# ISO_12V_to_20V.net
KiCad netlist of a schematic drawn in Altium Designer
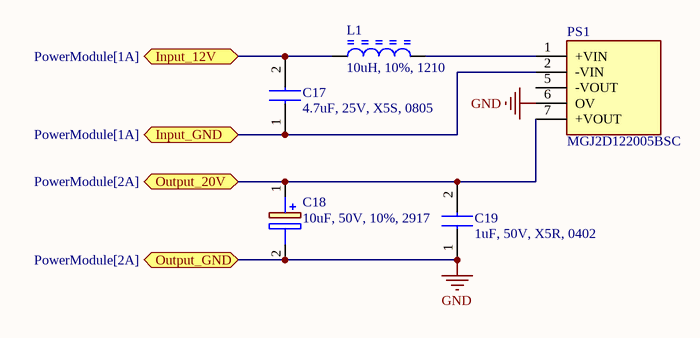
[diagram p0: ISO_12V_to_20V.SchDoc]

(export (version "E")
  (design (tool "Eeschema 10.0.6"))
  (components
    (comp (ref "C17")
      (value "4.7uF, 25V, X5S, 0805")
      (footprint "SamacSys:CAPC2012X145N")
      (description "Capacitor")
      (fields
        (field (name "MANUFACTURER_PART_NUMBER") "GRM21BC71E475KE11L")
        (field (name "MOUSER PART NUMBER") "81-GRM21BC71E475KE1L")
      )
      (libsource (lib "*") (part "GRM21BC71E475KE11L"))
    )
    (comp (ref "C18")
      (value "10uF, 50V, 10%, 2917")
      (footprint "SamacSys:T491D")
      (description "Capacitor Polarised")
      (fields
        (field (name "MANUFACTURER_PART_NUMBER") "T491D106K050AT")
        (field (name "MOUSER PART NUMBER") "80-T491D106K050")
      )
      (libsource (lib "*") (part "T491D106K050AT"))
    )
    (comp (ref "C19")
      (value "1uF, 50V, X5R, 0402")
      (footprint "SamacSys:GRM15x")
      (description "Capacitor")
      (fields
        (field (name "MANUFACTURER_PART_NUMBER") "GRM155R61H105KE05J")
        (field (name "MOUSER PART NUMBER") "81-GRM155R61H105KE5J")
      )
      (libsource (lib "*") (part "GRM155R61H105KE05J"))
    )
    (comp (ref "L1")
      (value "10uH, 10%, 1210")
      (footprint "BOUR-CM322522_V")
      (description "Chip Inductor\r\n, 10 uH, +/- 10%, -40 to 125 degC, 1210 (3225 Metric), RoHS, Tape and Reel")
      (libsource (lib "Altium Content Vault") (part "BOUR-IND-2A"))
    )
    (comp (ref "PS1")
      (value "MGJ2D122005BSC")
      (footprint "SamacSys:MGJ2D122005BSC")
      (description "Power Supply")
      (libsource (lib "*") (part "MGJ2D122005BSC"))
    )
  )
  (nets
    (net (code "1") (name "/Input_12V") (class "Default")
      (node (ref "C17") (pin "2") (pinfunction "2_2") (pintype "passive"))
      (node (ref "L1") (pin "1") (pinfunction "1_1") (pintype "passive"))
    )
    (net (code "2") (name "/Input_GND") (class "Default")
      (node (ref "C17") (pin "1") (pinfunction "1_1") (pintype "passive"))
      (node (ref "PS1") (pin "2") (pinfunction "-VIN_2") (pintype "passive"))
    )
    (net (code "3") (name "/Output_20V") (class "Default")
      (node (ref "C18") (pin "1") (pinfunction "+_1") (pintype "passive"))
      (node (ref "C19") (pin "2") (pinfunction "2_2") (pintype "passive"))
      (node (ref "PS1") (pin "7") (pinfunction "+VOUT_7") (pintype "passive"))
    )
    (net (code "4") (name "GND") (class "Default")
      (node (ref "C18") (pin "2") (pinfunction "-_2") (pintype "passive"))
      (node (ref "C19") (pin "1") (pinfunction "1_1") (pintype "passive"))
      (node (ref "PS1") (pin "6") (pinfunction "OV_6") (pintype "passive"))
    )
    (net (code "5") (name "Net-(PS1-+VIN)") (class "Default")
      (node (ref "L1") (pin "2") (pinfunction "2_2") (pintype "passive"))
      (node (ref "PS1") (pin "1") (pinfunction "+VIN_1") (pintype "passive"))
    )
    (net (code "6") (name "unconnected-(PS1--VOUT-Pad5)") (class "Default")
      (node (ref "PS1") (pin "5") (pinfunction "-VOUT_5") (pintype "passive"))
    )
  )
)
